# GPSDO_FRONT.net
KiCad netlist of a schematic drawn in Altium Designer
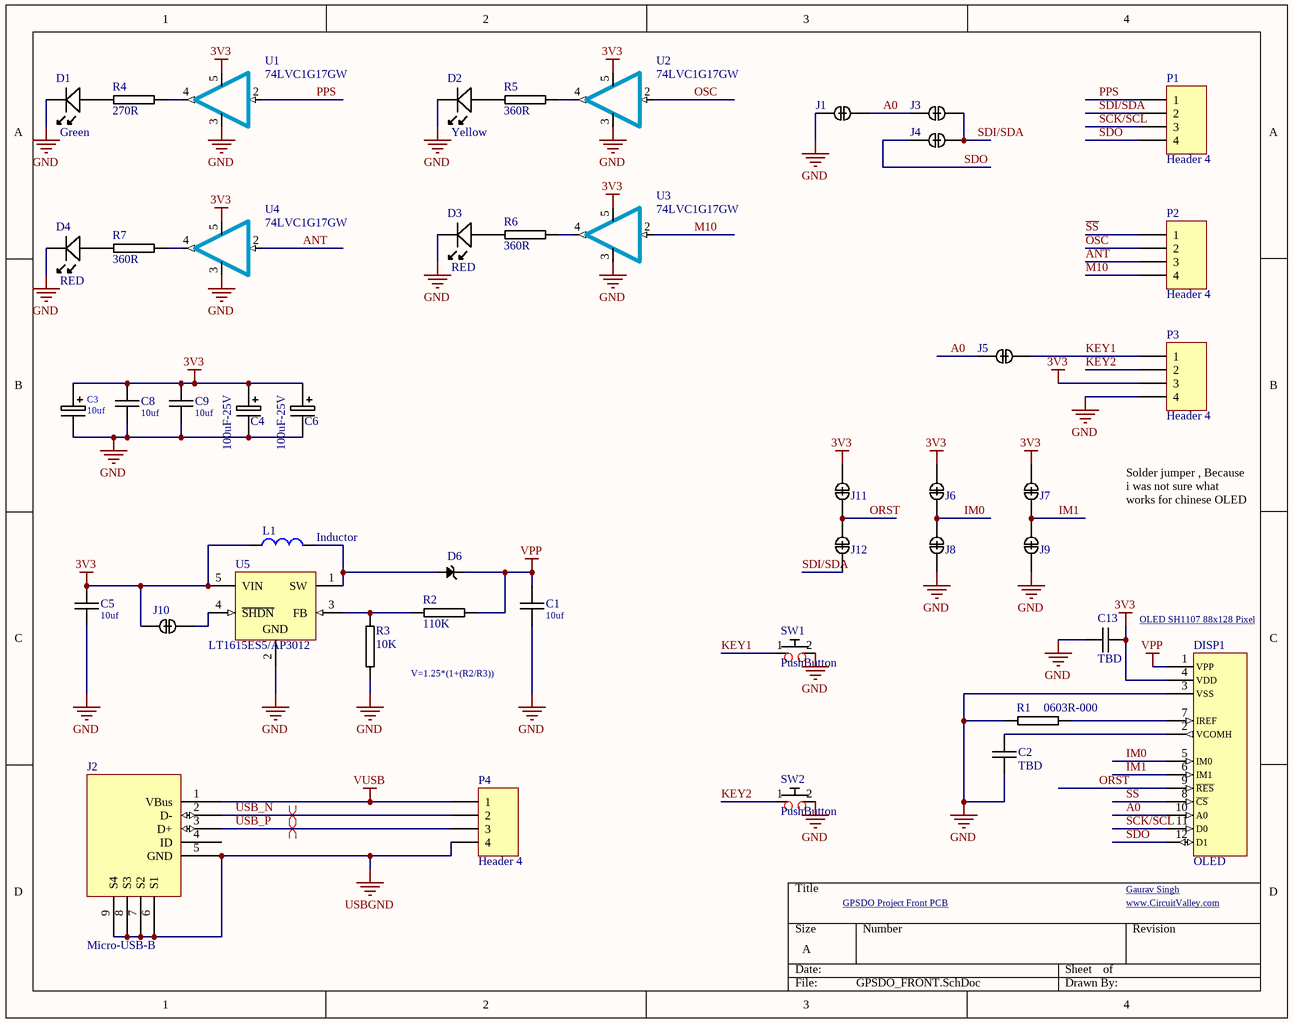
[diagram p0: GPSDO_FRONT.SchDoc]

(export (version "E")
  (design (tool "Eeschema 10.0.6"))
  (components
    (comp (ref "C1")
      (value "10uf")
      (footprint "1210C-GENERIC")
      (description "GENERIC CAPACITOR NON POLARISED 1210")
      (fields
        (field (name "MANUFACTURER") "Panasonic - ECG")
        (field (name "MANUFACTURER PART NUMBER") "ECJ-4YB0J226M")
      )
      (libsource (lib "Generic") (part "1210C-2u2-35V"))
    )
    (comp (ref "C2")
      (value "TBD")
      (footprint "0805C-TBD")
      (description "CAPACITOR 0805 CERAMIC VALUE TO BE DETERMINED")
      (libsource (lib "Generic") (part "0805C-TBD"))
    )
    (comp (ref "C3")
      (value "10uf")
      (footprint "CAPMP3528X210N")
      (description "Capacitor SMD Tantalum 47uF 20% 6.3V 1210")
      (fields (field (name "TOLERANCE") "±20%"))
      (libsource (lib "PBL - Capacitors") (part "CAPT_47u_1210_6V3"))
    )
    (comp (ref "C4")
      (value "100uF-25V")
      (footprint "PANACAP-D-GENERIC")
      (description "GENERIC CAPACITOR POLARISED")
      (libsource (lib "Generic") (part "PANACAP-100UF-16V-FK"))
    )
    (comp (ref "C5")
      (value "10uf")
      (footprint "1210C-GENERIC")
      (description "GENERIC CAPACITOR NON POLARISED 1210")
      (fields
        (field (name "MANUFACTURER") "Panasonic - ECG")
        (field (name "MANUFACTURER PART NUMBER") "ECJ-4YB0J226M")
      )
      (libsource (lib "Generic") (part "1210C-2u2-35V"))
    )
    (comp (ref "C6")
      (value "100uF-25V")
      (footprint "PANACAP-D-GENERIC")
      (description "GENERIC CAPACITOR POLARISED")
      (libsource (lib "Generic") (part "PANACAP-100UF-16V-FK"))
    )
    (comp (ref "C8")
      (value "10uf")
      (footprint "1210C-GENERIC")
      (description "GENERIC CAPACITOR NON POLARISED 1210")
      (fields
        (field (name "MANUFACTURER") "Panasonic - ECG")
        (field (name "MANUFACTURER PART NUMBER") "ECJ-4YB0J226M")
      )
      (libsource (lib "Generic") (part "1210C-2u2-35V"))
    )
    (comp (ref "C9")
      (value "10uf")
      (footprint "1210C-GENERIC")
      (description "GENERIC CAPACITOR NON POLARISED 1210")
      (fields
        (field (name "MANUFACTURER") "Panasonic - ECG")
        (field (name "MANUFACTURER PART NUMBER") "ECJ-4YB0J226M")
      )
      (libsource (lib "Generic") (part "1210C-2u2-35V"))
    )
    (comp (ref "C13")
      (value "TBD")
      (footprint "0805C-TBD")
      (description "CAPACITOR 0805 CERAMIC VALUE TO BE DETERMINED")
      (libsource (lib "Generic") (part "0805C-TBD"))
    )
    (comp (ref "D1")
      (value "Green")
      (footprint "KPTL-3216SURCK-01")
      (libsource (lib "reverse_led") (part "KPTL-3216SURCK-01"))
    )
    (comp (ref "D2")
      (value "Yellow")
      (footprint "KPTL-3216SURCK-01")
      (libsource (lib "reverse_led") (part "KPTL-3216SURCK-01"))
    )
    (comp (ref "D3")
      (value "RED")
      (footprint "KPTL-3216SURCK-01")
      (libsource (lib "reverse_led") (part "KPTL-3216SURCK-01"))
    )
    (comp (ref "D4")
      (value "RED")
      (footprint "KPTL-3216SURCK-01")
      (libsource (lib "reverse_led") (part "KPTL-3216SURCK-01"))
    )
    (comp (ref "D6") (value "~") (footprint "Diode_0603") (libsource (lib "cvlib") (part "Schottky_diode")))
    (comp (ref "DISP1")
      (value "OLED")
      (footprint "OLED QT1107P05C")
      (libsource (lib "cvlib") (part "OLED QT1107P05C"))
    )
    (comp (ref "J1")
      (value "BYPASS-MINI-CLOSED")
      (footprint "BYPASS-MINI-CLOSED")
      (description "SOLDERDOT BYPASS")
      (libsource (lib "Generic") (part "BYPASS-MINI-CLOSED"))
    )
    (comp (ref "J2")
      (value "Micro-USB-B")
      (footprint "10118193-0001lfc")
      (libsource (lib "USB-MICROB-HW-MC-5F") (part "Micro-USB-B"))
    )
    (comp (ref "J3")
      (value "BYPASS-MINI-CLOSED")
      (footprint "BYPASS-MINI-CLOSED")
      (description "SOLDERDOT BYPASS")
      (libsource (lib "Generic") (part "BYPASS-MINI-CLOSED"))
    )
    (comp (ref "J4")
      (value "BYPASS-MINI-CLOSED")
      (footprint "BYPASS-MINI-CLOSED")
      (description "SOLDERDOT BYPASS")
      (libsource (lib "Generic") (part "BYPASS-MINI-CLOSED"))
    )
    (comp (ref "J5")
      (value "BYPASS-MINI-CLOSED")
      (footprint "BYPASS-MINI-CLOSED")
      (description "SOLDERDOT BYPASS")
      (libsource (lib "Generic") (part "BYPASS-MINI-CLOSED"))
    )
    (comp (ref "J6")
      (value "BYPASS-MINI-CLOSED")
      (footprint "BYPASS-MINI-CLOSED")
      (description "SOLDERDOT BYPASS")
      (libsource (lib "Generic") (part "BYPASS-MINI-CLOSED"))
    )
    (comp (ref "J7")
      (value "BYPASS-MINI-CLOSED")
      (footprint "BYPASS-MINI-CLOSED")
      (description "SOLDERDOT BYPASS")
      (libsource (lib "Generic") (part "BYPASS-MINI-CLOSED"))
    )
    (comp (ref "J8")
      (value "BYPASS-MINI-CLOSED")
      (footprint "BYPASS-MINI-CLOSED")
      (description "SOLDERDOT BYPASS")
      (libsource (lib "Generic") (part "BYPASS-MINI-CLOSED"))
    )
    (comp (ref "J9")
      (value "BYPASS-MINI-CLOSED")
      (footprint "BYPASS-MINI-CLOSED")
      (description "SOLDERDOT BYPASS")
      (libsource (lib "Generic") (part "BYPASS-MINI-CLOSED"))
    )
    (comp (ref "J10")
      (value "BYPASS-MINI-CLOSED")
      (footprint "BYPASS-MINI-CLOSED")
      (description "SOLDERDOT BYPASS")
      (libsource (lib "Generic") (part "BYPASS-MINI-CLOSED"))
    )
    (comp (ref "J11")
      (value "BYPASS-MINI-CLOSED")
      (footprint "BYPASS-MINI-CLOSED")
      (description "SOLDERDOT BYPASS")
      (libsource (lib "Generic") (part "BYPASS-MINI-CLOSED"))
    )
    (comp (ref "J12")
      (value "BYPASS-MINI-CLOSED")
      (footprint "BYPASS-MINI-CLOSED")
      (description "SOLDERDOT BYPASS")
      (libsource (lib "Generic") (part "BYPASS-MINI-CLOSED"))
    )
    (comp (ref "L1")
      (value "Inductor")
      (footprint "IFSC-1515AH-01")
      (libsource (lib "Inductor") (part "inductor_smd"))
    )
    (comp (ref "P1")
      (value "Header 4")
      (footprint "M20-8770446 4PIN")
      (description "Header, 4-Pin")
      (fields (field (name "PUBLISHER") "Altium Limited"))
      (libsource (lib "Miscellaneous Connectors") (part "Header 4"))
    )
    (comp (ref "P2")
      (value "Header 4")
      (footprint "M20-8770446 4PIN")
      (description "Header, 4-Pin")
      (fields (field (name "PUBLISHER") "Altium Limited"))
      (libsource (lib "Miscellaneous Connectors") (part "Header 4"))
    )
    (comp (ref "P3")
      (value "Header 4")
      (footprint "M20-8770446 4PIN")
      (description "Header, 4-Pin")
      (fields (field (name "PUBLISHER") "Altium Limited"))
      (libsource (lib "Miscellaneous Connectors") (part "Header 4"))
    )
    (comp (ref "P4")
      (value "Header 4")
      (footprint "22-23-2041")
      (description "Header, 4-Pin")
      (fields (field (name "PUBLISHER") "Altium Limited"))
      (libsource (lib "Miscellaneous Connectors") (part "Header 4"))
    )
    (comp (ref "R1")
      (value "0603R-000")
      (footprint "0603R-GENERIC")
      (description "GENERIC RESISTOR 0603")
      (libsource (lib "Generic") (part "0603R-000"))
    )
    (comp (ref "R2")
      (value "110K")
      (footprint "0603R-GENERIC")
      (description "GENERIC RESISTOR 0603")
      (libsource (lib "Generic") (part "0603R-000"))
    )
    (comp (ref "R3")
      (value "10K")
      (footprint "0603R-GENERIC")
      (description "GENERIC RESISTOR 0603")
      (libsource (lib "Generic") (part "0603R-000"))
    )
    (comp (ref "R4")
      (value "270R")
      (footprint "0603R-GENERIC")
      (description "GENERIC RESISTOR 0603")
      (libsource (lib "Generic") (part "0603R-000"))
    )
    (comp (ref "R5")
      (value "360R")
      (footprint "0603R-GENERIC")
      (description "GENERIC RESISTOR 0603")
      (libsource (lib "Generic") (part "0603R-000"))
    )
    (comp (ref "R6")
      (value "360R")
      (footprint "0603R-GENERIC")
      (description "GENERIC RESISTOR 0603")
      (libsource (lib "Generic") (part "0603R-000"))
    )
    (comp (ref "R7")
      (value "360R")
      (footprint "0603R-GENERIC")
      (description "GENERIC RESISTOR 0603")
      (libsource (lib "Generic") (part "0603R-000"))
    )
    (comp (ref "SW1")
      (value "PushButton")
      (footprint "EVQ-11A04R")
      (libsource (lib "PushSwitchSmall") (part "PushButton"))
    )
    (comp (ref "SW2")
      (value "PushButton")
      (footprint "EVQ-11A04R")
      (libsource (lib "PushSwitchSmall") (part "PushButton"))
    )
    (comp (ref "U1")
      (value "74LVC1G17GW")
      (footprint "SC70-5")
      (libsource (lib "cvlib") (part "74LVC1G17GW-Q100"))
    )
    (comp (ref "U2")
      (value "74LVC1G17GW")
      (footprint "SC70-5")
      (libsource (lib "cvlib") (part "74LVC1G17GW-Q100"))
    )
    (comp (ref "U3")
      (value "74LVC1G17GW")
      (footprint "SC70-5")
      (libsource (lib "cvlib") (part "74LVC1G17GW-Q100"))
    )
    (comp (ref "U4")
      (value "74LVC1G17GW")
      (footprint "SC70-5")
      (libsource (lib "cvlib") (part "74LVC1G17GW-Q100"))
    )
    (comp (ref "U5")
      (value "LT1615ES5/AP3012")
      (footprint "LT-S5-5-TSOT-23_N")
      (description "Micropower Step-Up DC/DC Converter, 5-pin SOT23 (S5-5), -40 to 85 degC")
      (fields (field (name "MANUFACTURER") "Linear Technology") (field (name "PARTNUMBER") "LT1615ES5"))
      (libsource (lib "Linear Technology Power Management Switching Regulator LT1074-LT8705") (part "LT1615ES5"))
    )
  )
  (nets
    (net (code "1") (name "/A0") (class "Default")
      (node (ref "DISP1") (pin "10") (pinfunction "A0_10") (pintype "input"))
      (node (ref "J1") (pin "2") (pinfunction "2_2") (pintype "passive"))
      (node (ref "J3") (pin "1") (pinfunction "1_1") (pintype "passive"))
      (node (ref "J5") (pin "1") (pinfunction "1_1") (pintype "passive"))
    )
    (net (code "2") (name "/ANT") (class "Default")
      (node (ref "P2") (pin "3") (pinfunction "3_3") (pintype "passive"))
      (node (ref "U4") (pin "2") (pinfunction "2_2") (pintype "input"))
    )
    (net (code "3") (name "/IM0") (class "Default")
      (node (ref "DISP1") (pin "5") (pinfunction "IM0_5") (pintype "input"))
      (node (ref "J6") (pin "1") (pinfunction "1_1") (pintype "passive"))
      (node (ref "J8") (pin "2") (pinfunction "2_2") (pintype "passive"))
    )
    (net (code "4") (name "/IM1") (class "Default")
      (node (ref "DISP1") (pin "6") (pinfunction "IM1_6") (pintype "input"))
      (node (ref "J7") (pin "1") (pinfunction "1_1") (pintype "passive"))
      (node (ref "J9") (pin "2") (pinfunction "2_2") (pintype "passive"))
    )
    (net (code "5") (name "/KEY1") (class "Default")
      (node (ref "J5") (pin "2") (pinfunction "2_2") (pintype "passive"))
      (node (ref "P3") (pin "1") (pinfunction "1_1") (pintype "passive"))
      (node (ref "SW1") (pin "1") (pinfunction "P1_1") (pintype "passive"))
    )
    (net (code "6") (name "/KEY2") (class "Default")
      (node (ref "P3") (pin "2") (pinfunction "2_2") (pintype "passive"))
      (node (ref "SW2") (pin "1") (pinfunction "P1_1") (pintype "passive"))
    )
    (net (code "7") (name "/M10") (class "Default")
      (node (ref "P2") (pin "4") (pinfunction "4_4") (pintype "passive"))
      (node (ref "U3") (pin "2") (pinfunction "2_2") (pintype "input"))
    )
    (net (code "8") (name "/ORST") (class "Default")
      (node (ref "DISP1") (pin "9") (pinfunction "~{RES}_9") (pintype "input"))
      (node (ref "J11") (pin "1") (pinfunction "1_1") (pintype "passive"))
      (node (ref "J12") (pin "2") (pinfunction "2_2") (pintype "passive"))
    )
    (net (code "9") (name "/OSC") (class "Default")
      (node (ref "P2") (pin "2") (pinfunction "2_2") (pintype "passive"))
      (node (ref "U2") (pin "2") (pinfunction "2_2") (pintype "input"))
    )
    (net (code "10") (name "/PPS") (class "Default")
      (node (ref "P1") (pin "1") (pinfunction "1_1") (pintype "passive"))
      (node (ref "U1") (pin "2") (pinfunction "2_2") (pintype "input"))
    )
    (net (code "11") (name "/SCK{slash}SCL") (class "Default")
      (node (ref "DISP1") (pin "11") (pinfunction "D0_11") (pintype "input"))
      (node (ref "P1") (pin "3") (pinfunction "3_3") (pintype "passive"))
    )
    (net (code "12") (name "/SDI{slash}SDA") (class "Default")
      (node (ref "J12") (pin "1") (pinfunction "1_1") (pintype "passive"))
      (node (ref "J3") (pin "2") (pinfunction "2_2") (pintype "passive"))
      (node (ref "J4") (pin "1") (pinfunction "1_1") (pintype "passive"))
      (node (ref "P1") (pin "2") (pinfunction "2_2") (pintype "passive"))
    )
    (net (code "13") (name "/SDO") (class "Default")
      (node (ref "DISP1") (pin "12") (pinfunction "D1_12") (pintype "bidirectional"))
      (node (ref "J4") (pin "2") (pinfunction "2_2") (pintype "passive"))
      (node (ref "P1") (pin "4") (pinfunction "4_4") (pintype "passive"))
    )
    (net (code "14") (name "/USB_N") (class "Default")
      (node (ref "J2") (pin "2") (pinfunction "D-_2") (pintype "bidirectional"))
      (node (ref "P4") (pin "2") (pinfunction "2_2") (pintype "passive"))
    )
    (net (code "15") (name "/USB_P") (class "Default")
      (node (ref "J2") (pin "3") (pinfunction "D+_3") (pintype "bidirectional"))
      (node (ref "P4") (pin "3") (pinfunction "3_3") (pintype "passive"))
    )
    (net (code "16") (name "/~{SS}") (class "Default")
      (node (ref "DISP1") (pin "8") (pinfunction "~{CS}_8") (pintype "input"))
      (node (ref "P2") (pin "1") (pinfunction "1_1") (pintype "passive"))
    )
    (net (code "17") (name "3V3") (class "Default")
      (node (ref "C13") (pin "2") (pintype "passive"))
      (node (ref "C3") (pin "1") (pintype "passive"))
      (node (ref "C4") (pin "+") (pinfunction "+_+") (pintype "passive"))
      (node (ref "C5") (pin "2") (pintype "passive"))
      (node (ref "C6") (pin "+") (pinfunction "+_+") (pintype "passive"))
      (node (ref "C8") (pin "2") (pintype "passive"))
      (node (ref "C9") (pin "2") (pintype "passive"))
      (node (ref "DISP1") (pin "4") (pinfunction "VDD_4") (pintype "power_in"))
      (node (ref "J10") (pin "2") (pinfunction "2_2") (pintype "passive"))
      (node (ref "J11") (pin "2") (pinfunction "2_2") (pintype "passive"))
      (node (ref "J6") (pin "2") (pinfunction "2_2") (pintype "passive"))
      (node (ref "J7") (pin "2") (pinfunction "2_2") (pintype "passive"))
      (node (ref "L1") (pin "1") (pinfunction "1_1") (pintype "passive"))
      (node (ref "P3") (pin "3") (pinfunction "3_3") (pintype "passive"))
      (node (ref "U1") (pin "5") (pinfunction "VCC_5") (pintype "power_in"))
      (node (ref "U2") (pin "5") (pinfunction "VCC_5") (pintype "power_in"))
      (node (ref "U3") (pin "5") (pinfunction "VCC_5") (pintype "power_in"))
      (node (ref "U4") (pin "5") (pinfunction "VCC_5") (pintype "power_in"))
      (node (ref "U5") (pin "5") (pinfunction "VIN_5") (pintype "power_in"))
    )
    (net (code "18") (name "GND") (class "Default")
      (node (ref "C1") (pin "1") (pintype "passive"))
      (node (ref "C13") (pin "1") (pintype "passive"))
      (node (ref "C2") (pin "1") (pintype "passive"))
      (node (ref "C3") (pin "2") (pintype "passive"))
      (node (ref "C4") (pin "-") (pinfunction "-_-") (pintype "passive"))
      (node (ref "C5") (pin "1") (pintype "passive"))
      (node (ref "C6") (pin "-") (pinfunction "-_-") (pintype "passive"))
      (node (ref "C8") (pin "1") (pintype "passive"))
      (node (ref "C9") (pin "1") (pintype "passive"))
      (node (ref "D1") (pin "K") (pinfunction "K_K") (pintype "passive"))
      (node (ref "D2") (pin "K") (pinfunction "K_K") (pintype "passive"))
      (node (ref "D3") (pin "K") (pinfunction "K_K") (pintype "passive"))
      (node (ref "D4") (pin "K") (pinfunction "K_K") (pintype "passive"))
      (node (ref "DISP1") (pin "3") (pinfunction "VSS_3") (pintype "passive"))
      (node (ref "J1") (pin "1") (pinfunction "1_1") (pintype "passive"))
      (node (ref "J8") (pin "1") (pinfunction "1_1") (pintype "passive"))
      (node (ref "J9") (pin "1") (pinfunction "1_1") (pintype "passive"))
      (node (ref "P3") (pin "4") (pinfunction "4_4") (pintype "passive"))
      (node (ref "R1") (pin "1") (pintype "passive"))
      (node (ref "R3") (pin "1") (pintype "passive"))
      (node (ref "SW1") (pin "2") (pinfunction "P2_2") (pintype "passive"))
      (node (ref "SW2") (pin "2") (pinfunction "P2_2") (pintype "passive"))
      (node (ref "U1") (pin "3") (pinfunction "GND_3") (pintype "passive"))
      (node (ref "U2") (pin "3") (pinfunction "GND_3") (pintype "passive"))
      (node (ref "U3") (pin "3") (pinfunction "GND_3") (pintype "passive"))
      (node (ref "U4") (pin "3") (pinfunction "GND_3") (pintype "passive"))
      (node (ref "U5") (pin "2") (pinfunction "GND_2") (pintype "power_in"))
    )
    (net (code "19") (name "Net-(D1-PadA)") (class "Default")
      (node (ref "D1") (pin "A") (pinfunction "A_A") (pintype "passive"))
      (node (ref "R4") (pin "1") (pintype "passive"))
    )
    (net (code "20") (name "Net-(D2-PadA)") (class "Default")
      (node (ref "D2") (pin "A") (pinfunction "A_A") (pintype "passive"))
      (node (ref "R5") (pin "1") (pintype "passive"))
    )
    (net (code "21") (name "Net-(D3-PadA)") (class "Default")
      (node (ref "D3") (pin "A") (pinfunction "A_A") (pintype "passive"))
      (node (ref "R6") (pin "1") (pintype "passive"))
    )
    (net (code "22") (name "Net-(D4-PadA)") (class "Default")
      (node (ref "D4") (pin "A") (pinfunction "A_A") (pintype "passive"))
      (node (ref "R7") (pin "1") (pintype "passive"))
    )
    (net (code "23") (name "Net-(DISP1-IREF)") (class "Default")
      (node (ref "DISP1") (pin "7") (pinfunction "IREF_7") (pintype "input"))
      (node (ref "R1") (pin "2") (pintype "passive"))
    )
    (net (code "24") (name "Net-(DISP1-VCOMH)") (class "Default")
      (node (ref "C2") (pin "2") (pintype "passive"))
      (node (ref "DISP1") (pin "2") (pinfunction "VCOMH_2") (pintype "output"))
    )
    (net (code "25") (name "Net-(U1-3)") (class "Default")
      (node (ref "R4") (pin "2") (pintype "passive"))
      (node (ref "U1") (pin "4") (pinfunction "3_4") (pintype "output"))
    )
    (net (code "26") (name "Net-(U2-3)") (class "Default")
      (node (ref "R5") (pin "2") (pintype "passive"))
      (node (ref "U2") (pin "4") (pinfunction "3_4") (pintype "output"))
    )
    (net (code "27") (name "Net-(U3-3)") (class "Default")
      (node (ref "R6") (pin "2") (pintype "passive"))
      (node (ref "U3") (pin "4") (pinfunction "3_4") (pintype "output"))
    )
    (net (code "28") (name "Net-(U4-3)") (class "Default")
      (node (ref "R7") (pin "2") (pintype "passive"))
      (node (ref "U4") (pin "4") (pinfunction "3_4") (pintype "output"))
    )
    (net (code "29") (name "Net-(U5-FB)") (class "Default")
      (node (ref "R2") (pin "1") (pintype "passive"))
      (node (ref "R3") (pin "2") (pintype "passive"))
      (node (ref "U5") (pin "3") (pinfunction "FB_3") (pintype "input"))
    )
    (net (code "30") (name "Net-(U5-SW)") (class "Default")
      (node (ref "D6") (pin "1") (pinfunction "1_1") (pintype "passive"))
      (node (ref "L1") (pin "2") (pinfunction "2_2") (pintype "passive"))
      (node (ref "U5") (pin "1") (pinfunction "SW_1") (pintype "power_in"))
    )
    (net (code "31") (name "Net-(U5-~{SHDN})") (class "Default")
      (node (ref "J10") (pin "1") (pinfunction "1_1") (pintype "passive"))
      (node (ref "U5") (pin "4") (pinfunction "~{SHDN}_4") (pintype "input"))
    )
    (net (code "32") (name "USBGND") (class "Default")
      (node (ref "J2") (pin "5") (pinfunction "GND_5") (pintype "power_in"))
      (node (ref "J2") (pin "6") (pinfunction "S1_6") (pintype "passive"))
      (node (ref "J2") (pin "7") (pinfunction "S2_7") (pintype "power_in"))
      (node (ref "J2") (pin "8") (pinfunction "S3_8") (pintype "power_in"))
      (node (ref "J2") (pin "9") (pinfunction "S4_9") (pintype "power_in"))
      (node (ref "P4") (pin "4") (pinfunction "4_4") (pintype "passive"))
    )
    (net (code "33") (name "VPP") (class "Default")
      (node (ref "C1") (pin "2") (pintype "passive"))
      (node (ref "D6") (pin "2") (pinfunction "2_2") (pintype "passive"))
      (node (ref "DISP1") (pin "1") (pinfunction "VPP_1") (pintype "power_in"))
      (node (ref "R2") (pin "2") (pintype "passive"))
    )
    (net (code "34") (name "VUSB") (class "Default")
      (node (ref "J2") (pin "1") (pinfunction "VBus_1") (pintype "power_in"))
      (node (ref "P4") (pin "1") (pinfunction "1_1") (pintype "passive"))
    )
    (net (code "35") (name "unconnected-(J2-ID-Pad4)") (class "Default")
      (node (ref "J2") (pin "4") (pinfunction "ID_4") (pintype "passive"))
    )
  )
)
